# TOP.net
KiCad netlist of a schematic drawn in Altium Designer
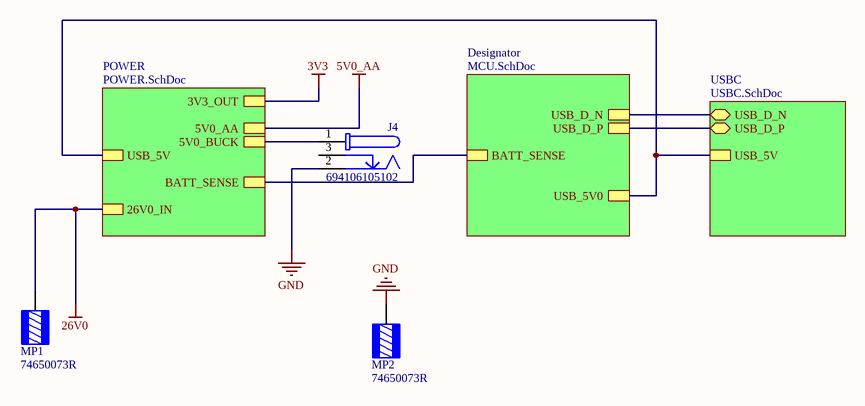
[diagram p0: TOP.SchDoc]

(export (version "E")
  (design (tool "Eeschema 10.0.6"))
  (components
    (comp (ref "J4")
      (value "694106105102")
      (footprint "694106105102")
      (description "DC Power Jack Connector with Pegs WR-DC, Male, Right Angled, SMT, 5 A, 24 V")
      (libsource (lib "Altium Content Vault") (part "DC Power Jack"))
    )
    (comp (ref "MP1")
      (value "74650073R")
      (footprint "WURTH 74650073")
      (description "TERM REDCUBE M3 4PIN PCB")
      (fields (field (name "MANUFACTURER") "Würth Elektronik"))
      (libsource (lib "Celestial Altium Library - altium_library") (part "MOUNTING POINT"))
    )
    (comp (ref "MP2")
      (value "74650073R")
      (footprint "WURTH 74650073")
      (description "TERM REDCUBE M3 4PIN PCB")
      (fields (field (name "MANUFACTURER") "Würth Elektronik"))
      (libsource (lib "Celestial Altium Library - altium_library") (part "MOUNTING POINT"))
    )
  )
  (nets
    (net (code "1") (name "/5V0_BUCK") (class "Default")
      (node (ref "J4") (pin "1") (pinfunction "1_1") (pintype "passive"))
    )
    (net (code "8") (name "26V0") (class "Default")
      (node (ref "MP1") (pin "1") (pinfunction "1_1") (pintype "passive"))
    )
    (net (code "9") (name "GND") (class "Default")
      (node (ref "J4") (pin "2") (pinfunction "2_2") (pintype "passive"))
      (node (ref "MP2") (pin "1") (pinfunction "1_1") (pintype "passive"))
    )
    (net (code "10") (name "unconnected-(J4-Pad3)") (class "Default")
      (node (ref "J4") (pin "3") (pinfunction "3_3") (pintype "passive"))
    )
  )
)
